# B683X.net
KiCad netlist of a schematic drawn in EAGLE
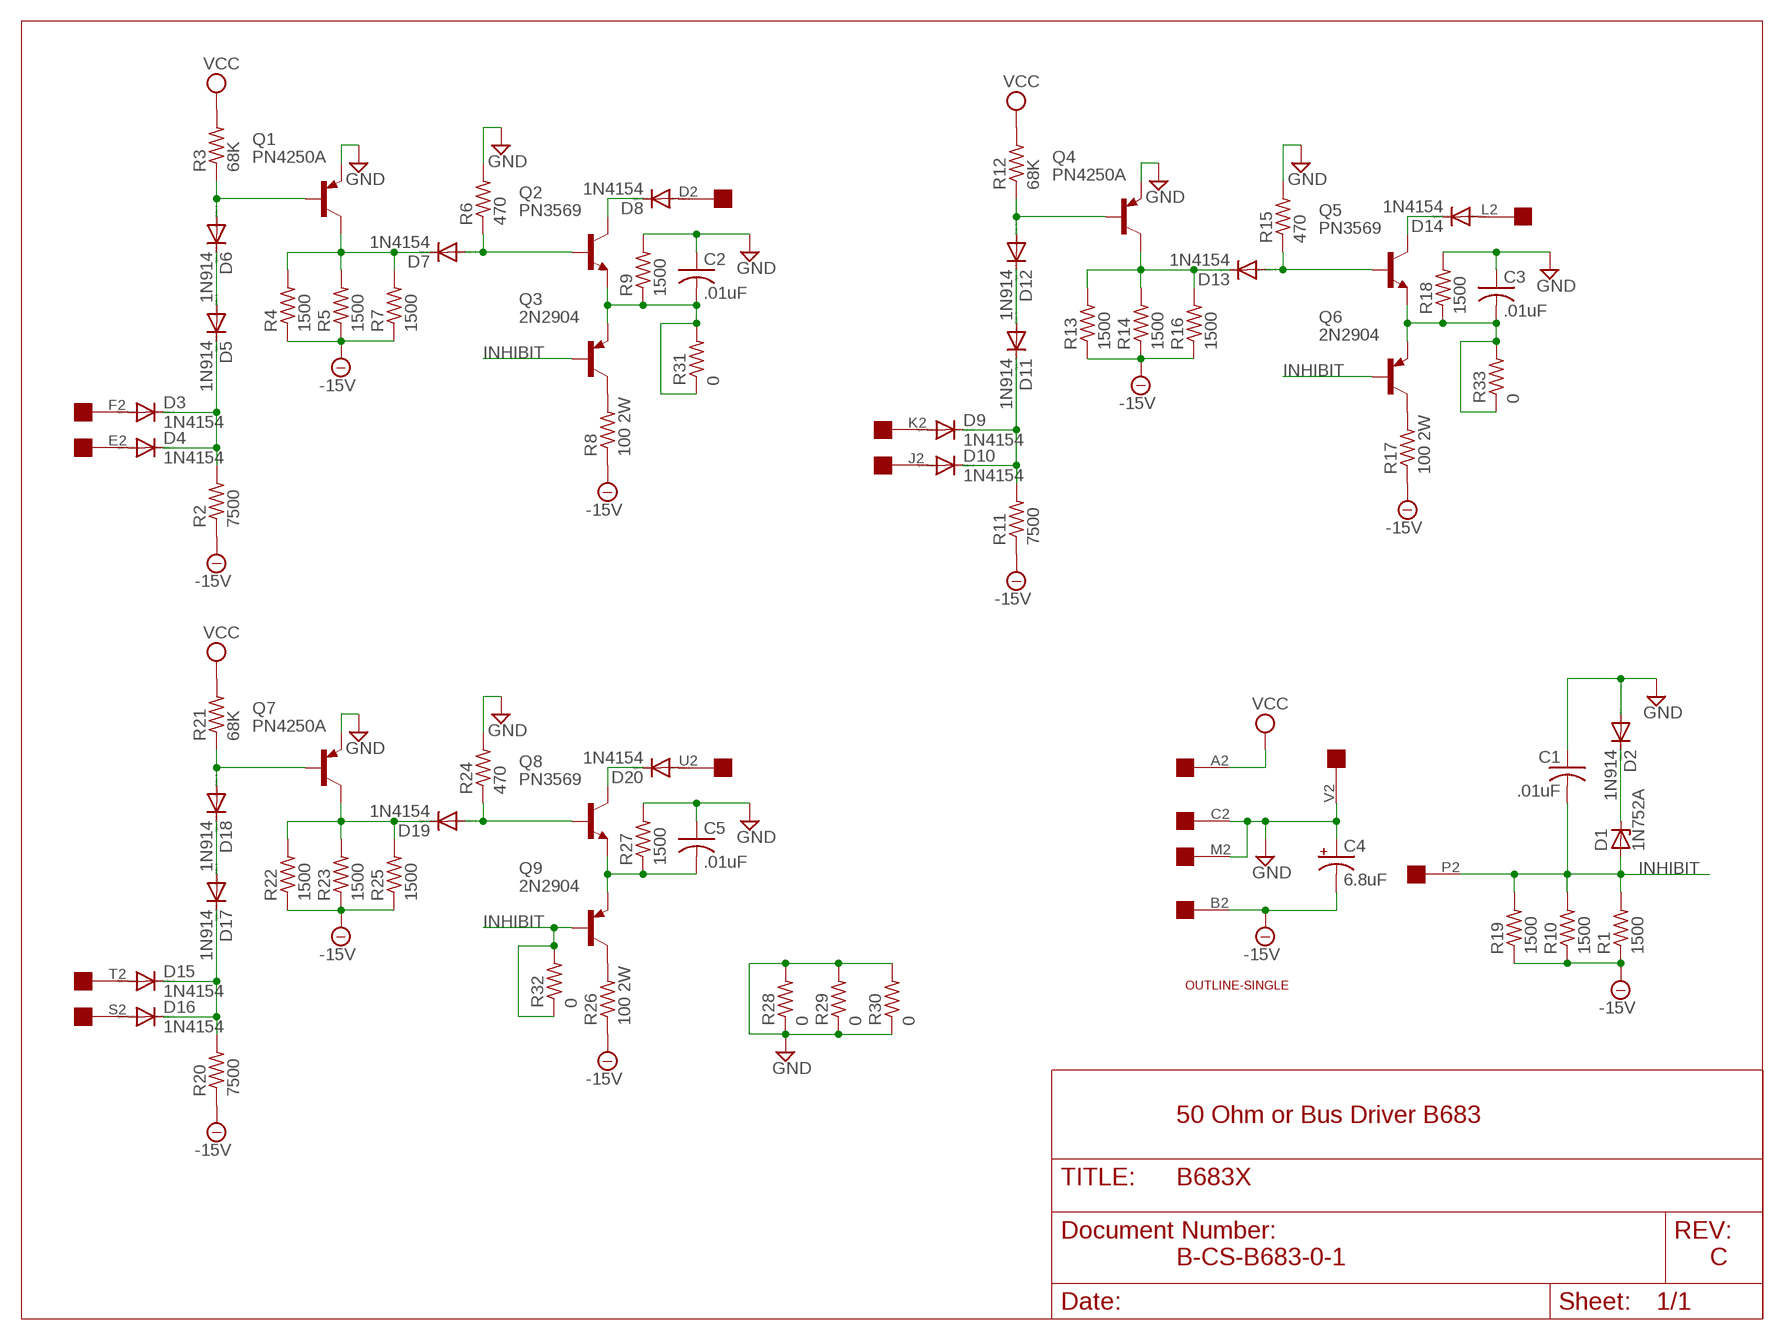
[diagram p0: schematic, sheet 1]

(export (version "E")
  (design (tool "Eeschema 10.0.6"))
  (components
    (comp (ref "C1")
      (value ".01uF")
      (footprint "eagle-import:C063-025X075")
      (libsource (lib "eagle-import") (part "C-US"))
    )
    (comp (ref "C2")
      (value ".01uF")
      (footprint "eagle-import:C063-025X075")
      (libsource (lib "eagle-import") (part "C-US"))
    )
    (comp (ref "C3")
      (value ".01uF")
      (footprint "eagle-import:C063-025X075")
      (libsource (lib "eagle-import") (part "C-US"))
    )
    (comp (ref "C4")
      (value "6.8uF")
      (footprint "eagle-import:E12-8")
      (libsource (lib "eagle-import") (part "CPOL-USE20-8AXIAL"))
    )
    (comp (ref "C5")
      (value ".01uF")
      (footprint "eagle-import:C063-025X075")
      (libsource (lib "eagle-import") (part "C-US"))
    )
    (comp (ref "D1")
      (value "1N752A")
      (footprint "eagle-import:DO35Z10")
      (libsource (lib "eagle-import") (part "ZENER-DIODEDO35Z10"))
    )
    (comp (ref "D2")
      (value "1N914")
      (footprint "eagle-import:DO35-10")
      (libsource (lib "eagle-import") (part "DIODE-DO35-10"))
    )
    (comp (ref "D3")
      (value "1N4154")
      (footprint "eagle-import:DO35-10")
      (libsource (lib "eagle-import") (part "DIODE-DO35-10"))
    )
    (comp (ref "D4")
      (value "1N4154")
      (footprint "eagle-import:DO35-10")
      (libsource (lib "eagle-import") (part "DIODE-DO35-10"))
    )
    (comp (ref "D5")
      (value "1N914")
      (footprint "eagle-import:DO35-10")
      (libsource (lib "eagle-import") (part "DIODE-DO35-10"))
    )
    (comp (ref "D6")
      (value "1N914")
      (footprint "eagle-import:DO35-10")
      (libsource (lib "eagle-import") (part "DIODE-DO35-10"))
    )
    (comp (ref "D7")
      (value "1N4154")
      (footprint "eagle-import:DO35-10")
      (libsource (lib "eagle-import") (part "DIODE-DO35-10"))
    )
    (comp (ref "D8")
      (value "1N4154")
      (footprint "eagle-import:DO35-10")
      (libsource (lib "eagle-import") (part "DIODE-DO35-10"))
    )
    (comp (ref "D9")
      (value "1N4154")
      (footprint "eagle-import:DO35-10")
      (libsource (lib "eagle-import") (part "DIODE-DO35-10"))
    )
    (comp (ref "D10")
      (value "1N4154")
      (footprint "eagle-import:DO35-10")
      (libsource (lib "eagle-import") (part "DIODE-DO35-10"))
    )
    (comp (ref "D11")
      (value "1N914")
      (footprint "eagle-import:DO35-10")
      (libsource (lib "eagle-import") (part "DIODE-DO35-10"))
    )
    (comp (ref "D12")
      (value "1N914")
      (footprint "eagle-import:DO35-10")
      (libsource (lib "eagle-import") (part "DIODE-DO35-10"))
    )
    (comp (ref "D13")
      (value "1N4154")
      (footprint "eagle-import:DO35-10")
      (libsource (lib "eagle-import") (part "DIODE-DO35-10"))
    )
    (comp (ref "D14")
      (value "1N4154")
      (footprint "eagle-import:DO35-10")
      (libsource (lib "eagle-import") (part "DIODE-DO35-10"))
    )
    (comp (ref "D15")
      (value "1N4154")
      (footprint "eagle-import:DO35-10")
      (libsource (lib "eagle-import") (part "DIODE-DO35-10"))
    )
    (comp (ref "D16")
      (value "1N4154")
      (footprint "eagle-import:DO35-10")
      (libsource (lib "eagle-import") (part "DIODE-DO35-10"))
    )
    (comp (ref "D17")
      (value "1N914")
      (footprint "eagle-import:DO35-10")
      (libsource (lib "eagle-import") (part "DIODE-DO35-10"))
    )
    (comp (ref "D18")
      (value "1N914")
      (footprint "eagle-import:DO35-10")
      (libsource (lib "eagle-import") (part "DIODE-DO35-10"))
    )
    (comp (ref "D19")
      (value "1N4154")
      (footprint "eagle-import:DO35-10")
      (libsource (lib "eagle-import") (part "DIODE-DO35-10"))
    )
    (comp (ref "D20")
      (value "1N4154")
      (footprint "eagle-import:DO35-10")
      (libsource (lib "eagle-import") (part "DIODE-DO35-10"))
    )
    (comp (ref "Q1")
      (value "PN4250A")
      (footprint "eagle-import:TO5")
      (libsource (lib "eagle-import") (part "-PNP-TO5"))
    )
    (comp (ref "Q2")
      (value "PN3569")
      (footprint "eagle-import:TO5")
      (libsource (lib "eagle-import") (part "-NPN-TO5"))
    )
    (comp (ref "Q3")
      (value "2N2904")
      (footprint "eagle-import:TO5")
      (libsource (lib "eagle-import") (part "-PNP-TO5"))
    )
    (comp (ref "Q4")
      (value "PN4250A")
      (footprint "eagle-import:TO5")
      (libsource (lib "eagle-import") (part "-PNP-TO5"))
    )
    (comp (ref "Q5")
      (value "PN3569")
      (footprint "eagle-import:TO5")
      (libsource (lib "eagle-import") (part "-NPN-TO5"))
    )
    (comp (ref "Q6")
      (value "2N2904")
      (footprint "eagle-import:TO5")
      (libsource (lib "eagle-import") (part "-PNP-TO5"))
    )
    (comp (ref "Q7")
      (value "PN4250A")
      (footprint "eagle-import:TO5")
      (libsource (lib "eagle-import") (part "-PNP-TO5"))
    )
    (comp (ref "Q8")
      (value "PN3569")
      (footprint "eagle-import:TO5")
      (libsource (lib "eagle-import") (part "-NPN-TO5"))
    )
    (comp (ref "Q9")
      (value "2N2904")
      (footprint "eagle-import:TO5")
      (libsource (lib "eagle-import") (part "-PNP-TO5"))
    )
    (comp (ref "R1")
      (value "1500")
      (footprint "eagle-import:0207_10")
      (libsource (lib "eagle-import") (part "R-US_0207/10"))
    )
    (comp (ref "R2")
      (value "7500")
      (footprint "eagle-import:0207_10")
      (libsource (lib "eagle-import") (part "R-US_0207/10"))
    )
    (comp (ref "R3")
      (value "68K")
      (footprint "eagle-import:0207_10")
      (libsource (lib "eagle-import") (part "R-US_0207/10"))
    )
    (comp (ref "R4")
      (value "1500")
      (footprint "eagle-import:0207_10")
      (libsource (lib "eagle-import") (part "R-US_0207/10"))
    )
    (comp (ref "R5")
      (value "1500")
      (footprint "eagle-import:0207_10")
      (libsource (lib "eagle-import") (part "R-US_0207/10"))
    )
    (comp (ref "R6")
      (value "470")
      (footprint "eagle-import:0207_10")
      (libsource (lib "eagle-import") (part "R-US_0207/10"))
    )
    (comp (ref "R7")
      (value "1500")
      (footprint "eagle-import:0207_10")
      (libsource (lib "eagle-import") (part "R-US_0207/10"))
    )
    (comp (ref "R8")
      (value "100 2W")
      (footprint "eagle-import:0818_25")
      (libsource (lib "eagle-import") (part "R-US_0818/25"))
    )
    (comp (ref "R9")
      (value "1500")
      (footprint "eagle-import:0207_10")
      (libsource (lib "eagle-import") (part "R-US_0207/10"))
    )
    (comp (ref "R10")
      (value "1500")
      (footprint "eagle-import:0207_10")
      (libsource (lib "eagle-import") (part "R-US_0207/10"))
    )
    (comp (ref "R11")
      (value "7500")
      (footprint "eagle-import:0207_10")
      (libsource (lib "eagle-import") (part "R-US_0207/10"))
    )
    (comp (ref "R12")
      (value "68K")
      (footprint "eagle-import:0207_10")
      (libsource (lib "eagle-import") (part "R-US_0207/10"))
    )
    (comp (ref "R13")
      (value "1500")
      (footprint "eagle-import:0207_10")
      (libsource (lib "eagle-import") (part "R-US_0207/10"))
    )
    (comp (ref "R14")
      (value "1500")
      (footprint "eagle-import:0207_10")
      (libsource (lib "eagle-import") (part "R-US_0207/10"))
    )
    (comp (ref "R15")
      (value "470")
      (footprint "eagle-import:0207_10")
      (libsource (lib "eagle-import") (part "R-US_0207/10"))
    )
    (comp (ref "R16")
      (value "1500")
      (footprint "eagle-import:0207_10")
      (libsource (lib "eagle-import") (part "R-US_0207/10"))
    )
    (comp (ref "R17")
      (value "100 2W")
      (footprint "eagle-import:0818_25")
      (libsource (lib "eagle-import") (part "R-US_0818/25"))
    )
    (comp (ref "R18")
      (value "1500")
      (footprint "eagle-import:0207_10")
      (libsource (lib "eagle-import") (part "R-US_0207/10"))
    )
    (comp (ref "R19")
      (value "1500")
      (footprint "eagle-import:0207_10")
      (libsource (lib "eagle-import") (part "R-US_0207/10"))
    )
    (comp (ref "R20")
      (value "7500")
      (footprint "eagle-import:0207_10")
      (libsource (lib "eagle-import") (part "R-US_0207/10"))
    )
    (comp (ref "R21")
      (value "68K")
      (footprint "eagle-import:0207_10")
      (libsource (lib "eagle-import") (part "R-US_0207/10"))
    )
    (comp (ref "R22")
      (value "1500")
      (footprint "eagle-import:0207_10")
      (libsource (lib "eagle-import") (part "R-US_0207/10"))
    )
    (comp (ref "R23")
      (value "1500")
      (footprint "eagle-import:0207_10")
      (libsource (lib "eagle-import") (part "R-US_0207/10"))
    )
    (comp (ref "R24")
      (value "470")
      (footprint "eagle-import:0207_10")
      (libsource (lib "eagle-import") (part "R-US_0207/10"))
    )
    (comp (ref "R25")
      (value "1500")
      (footprint "eagle-import:0207_10")
      (libsource (lib "eagle-import") (part "R-US_0207/10"))
    )
    (comp (ref "R26")
      (value "100 2W")
      (footprint "eagle-import:0818_25")
      (libsource (lib "eagle-import") (part "R-US_0818/25"))
    )
    (comp (ref "R27")
      (value "1500")
      (footprint "eagle-import:0207_10")
      (libsource (lib "eagle-import") (part "R-US_0207/10"))
    )
    (comp (ref "R28")
      (value "0")
      (footprint "eagle-import:0207_10")
      (libsource (lib "eagle-import") (part "R-US_0207/10"))
    )
    (comp (ref "R29")
      (value "0")
      (footprint "eagle-import:0207_10")
      (libsource (lib "eagle-import") (part "R-US_0207/10"))
    )
    (comp (ref "R30")
      (value "0")
      (footprint "eagle-import:0207_10")
      (libsource (lib "eagle-import") (part "R-US_0207/10"))
    )
    (comp (ref "R31")
      (value "0")
      (footprint "eagle-import:0207_10")
      (libsource (lib "eagle-import") (part "R-US_0207/10"))
    )
    (comp (ref "R32")
      (value "0")
      (footprint "eagle-import:0207_10")
      (libsource (lib "eagle-import") (part "R-US_0207/10"))
    )
    (comp (ref "R33")
      (value "0")
      (footprint "eagle-import:0207_10")
      (libsource (lib "eagle-import") (part "R-US_0207/10"))
    )
    (comp (ref "U$1")
      (value "OUTLINE-SINGLE")
      (footprint "eagle-import:SINGLE")
      (libsource (lib "eagle-import") (part "OUTLINE-SINGLE"))
    )
    (comp (ref "U$2")
      (value "EDGE-1")
      (footprint "eagle-import:EDGE-CON1")
      (libsource (lib "eagle-import") (part "EDGE-1"))
    )
  )
  (nets
    (net (code "1") (name "-15V") (class "Default")
      (node (ref "C4") (pin "-") (pinfunction "-_-") (pintype "passive"))
      (node (ref "R1") (pin "1") (pinfunction "1_1") (pintype "passive"))
      (node (ref "R10") (pin "1") (pinfunction "1_1") (pintype "passive"))
      (node (ref "R11") (pin "1") (pinfunction "1_1") (pintype "passive"))
      (node (ref "R13") (pin "1") (pinfunction "1_1") (pintype "passive"))
      (node (ref "R14") (pin "1") (pinfunction "1_1") (pintype "passive"))
      (node (ref "R16") (pin "1") (pinfunction "1_1") (pintype "passive"))
      (node (ref "R17") (pin "1") (pinfunction "1_1") (pintype "passive"))
      (node (ref "R19") (pin "1") (pinfunction "1_1") (pintype "passive"))
      (node (ref "R2") (pin "1") (pinfunction "1_1") (pintype "passive"))
      (node (ref "R20") (pin "1") (pinfunction "1_1") (pintype "passive"))
      (node (ref "R22") (pin "1") (pinfunction "1_1") (pintype "passive"))
      (node (ref "R23") (pin "1") (pinfunction "1_1") (pintype "passive"))
      (node (ref "R25") (pin "1") (pinfunction "1_1") (pintype "passive"))
      (node (ref "R26") (pin "1") (pinfunction "1_1") (pintype "passive"))
      (node (ref "R4") (pin "1") (pinfunction "1_1") (pintype "passive"))
      (node (ref "R5") (pin "1") (pinfunction "1_1") (pintype "passive"))
      (node (ref "R7") (pin "1") (pinfunction "1_1") (pintype "passive"))
      (node (ref "R8") (pin "1") (pinfunction "1_1") (pintype "passive"))
      (node (ref "U$2") (pin "B2") (pinfunction "1_B2") (pintype "bidirectional"))
    )
    (net (code "2") (name "/INHIBIT") (class "Default")
      (node (ref "C1") (pin "2") (pinfunction "2_2") (pintype "passive"))
      (node (ref "D1") (pin "A") (pinfunction "A_A") (pintype "passive"))
      (node (ref "Q3") (pin "2") (pinfunction "B_2") (pintype "passive"))
      (node (ref "Q6") (pin "2") (pinfunction "B_2") (pintype "passive"))
      (node (ref "Q9") (pin "2") (pinfunction "B_2") (pintype "passive"))
      (node (ref "R1") (pin "2") (pinfunction "2_2") (pintype "passive"))
      (node (ref "R10") (pin "2") (pinfunction "2_2") (pintype "passive"))
      (node (ref "R19") (pin "2") (pinfunction "2_2") (pintype "passive"))
      (node (ref "R32") (pin "1") (pinfunction "1_1") (pintype "passive"))
      (node (ref "R32") (pin "2") (pinfunction "2_2") (pintype "passive"))
      (node (ref "U$2") (pin "P2") (pinfunction "1_P2") (pintype "bidirectional"))
    )
    (net (code "3") (name "GND") (class "Default")
      (node (ref "C1") (pin "1") (pinfunction "1_1") (pintype "passive"))
      (node (ref "C2") (pin "1") (pinfunction "1_1") (pintype "passive"))
      (node (ref "C3") (pin "1") (pinfunction "1_1") (pintype "passive"))
      (node (ref "C4") (pin "+") (pinfunction "+_+") (pintype "passive"))
      (node (ref "C5") (pin "1") (pinfunction "1_1") (pintype "passive"))
      (node (ref "D2") (pin "A") (pinfunction "A_A") (pintype "passive"))
      (node (ref "Q1") (pin "1") (pinfunction "E_1") (pintype "passive"))
      (node (ref "Q4") (pin "1") (pinfunction "E_1") (pintype "passive"))
      (node (ref "Q7") (pin "1") (pinfunction "E_1") (pintype "passive"))
      (node (ref "R15") (pin "2") (pinfunction "2_2") (pintype "passive"))
      (node (ref "R18") (pin "2") (pinfunction "2_2") (pintype "passive"))
      (node (ref "R24") (pin "2") (pinfunction "2_2") (pintype "passive"))
      (node (ref "R27") (pin "2") (pinfunction "2_2") (pintype "passive"))
      (node (ref "R28") (pin "1") (pinfunction "1_1") (pintype "passive"))
      (node (ref "R28") (pin "2") (pinfunction "2_2") (pintype "passive"))
      (node (ref "R29") (pin "1") (pinfunction "1_1") (pintype "passive"))
      (node (ref "R29") (pin "2") (pinfunction "2_2") (pintype "passive"))
      (node (ref "R30") (pin "1") (pinfunction "1_1") (pintype "passive"))
      (node (ref "R30") (pin "2") (pinfunction "2_2") (pintype "passive"))
      (node (ref "R6") (pin "2") (pinfunction "2_2") (pintype "passive"))
      (node (ref "R9") (pin "2") (pinfunction "2_2") (pintype "passive"))
      (node (ref "U$2") (pin "C2") (pinfunction "1_C2") (pintype "bidirectional"))
      (node (ref "U$2") (pin "M2") (pinfunction "1_M2") (pintype "bidirectional"))
      (node (ref "U$2") (pin "V2") (pinfunction "1_V2") (pintype "bidirectional"))
    )
    (net (code "4") (name "Net-(D1-PadC)") (class "Default")
      (node (ref "D1") (pin "C") (pinfunction "C_C") (pintype "passive"))
      (node (ref "D2") (pin "C") (pinfunction "C_C") (pintype "passive"))
    )
    (net (code "5") (name "Net-(D3-PadC)") (class "Default")
      (node (ref "D3") (pin "C") (pinfunction "C_C") (pintype "passive"))
      (node (ref "D4") (pin "C") (pinfunction "C_C") (pintype "passive"))
      (node (ref "D5") (pin "C") (pinfunction "C_C") (pintype "passive"))
      (node (ref "R2") (pin "2") (pinfunction "2_2") (pintype "passive"))
    )
    (net (code "6") (name "Net-(D5-PadA)") (class "Default")
      (node (ref "D5") (pin "A") (pinfunction "A_A") (pintype "passive"))
      (node (ref "D6") (pin "C") (pinfunction "C_C") (pintype "passive"))
    )
    (net (code "7") (name "Net-(D10-PadC)") (class "Default")
      (node (ref "D10") (pin "C") (pinfunction "C_C") (pintype "passive"))
      (node (ref "D11") (pin "C") (pinfunction "C_C") (pintype "passive"))
      (node (ref "D9") (pin "C") (pinfunction "C_C") (pintype "passive"))
      (node (ref "R11") (pin "2") (pinfunction "2_2") (pintype "passive"))
    )
    (net (code "8") (name "Net-(D11-PadA)") (class "Default")
      (node (ref "D11") (pin "A") (pinfunction "A_A") (pintype "passive"))
      (node (ref "D12") (pin "C") (pinfunction "C_C") (pintype "passive"))
    )
    (net (code "9") (name "Net-(D15-PadC)") (class "Default")
      (node (ref "D15") (pin "C") (pinfunction "C_C") (pintype "passive"))
      (node (ref "D16") (pin "C") (pinfunction "C_C") (pintype "passive"))
      (node (ref "D17") (pin "C") (pinfunction "C_C") (pintype "passive"))
      (node (ref "R20") (pin "2") (pinfunction "2_2") (pintype "passive"))
    )
    (net (code "10") (name "Net-(D17-PadA)") (class "Default")
      (node (ref "D17") (pin "A") (pinfunction "A_A") (pintype "passive"))
      (node (ref "D18") (pin "C") (pinfunction "C_C") (pintype "passive"))
    )
    (net (code "11") (name "Net-(Q1-B)") (class "Default")
      (node (ref "D6") (pin "A") (pinfunction "A_A") (pintype "passive"))
      (node (ref "Q1") (pin "2") (pinfunction "B_2") (pintype "passive"))
      (node (ref "R3") (pin "1") (pinfunction "1_1") (pintype "passive"))
    )
    (net (code "12") (name "Net-(Q1-C)") (class "Default")
      (node (ref "D7") (pin "C") (pinfunction "C_C") (pintype "passive"))
      (node (ref "Q1") (pin "3") (pinfunction "C_3") (pintype "passive"))
      (node (ref "R4") (pin "2") (pinfunction "2_2") (pintype "passive"))
      (node (ref "R5") (pin "2") (pinfunction "2_2") (pintype "passive"))
      (node (ref "R7") (pin "2") (pinfunction "2_2") (pintype "passive"))
    )
    (net (code "13") (name "Net-(Q2-B)") (class "Default")
      (node (ref "D7") (pin "A") (pinfunction "A_A") (pintype "passive"))
      (node (ref "Q2") (pin "2") (pinfunction "B_2") (pintype "passive"))
      (node (ref "R6") (pin "1") (pinfunction "1_1") (pintype "passive"))
    )
    (net (code "14") (name "Net-(Q2-C)") (class "Default")
      (node (ref "D8") (pin "C") (pinfunction "C_C") (pintype "passive"))
      (node (ref "Q2") (pin "3") (pinfunction "C_3") (pintype "passive"))
    )
    (net (code "15") (name "Net-(Q2-E)") (class "Default")
      (node (ref "C2") (pin "2") (pinfunction "2_2") (pintype "passive"))
      (node (ref "Q2") (pin "1") (pinfunction "E_1") (pintype "passive"))
      (node (ref "Q3") (pin "1") (pinfunction "E_1") (pintype "passive"))
      (node (ref "R31") (pin "1") (pinfunction "1_1") (pintype "passive"))
      (node (ref "R31") (pin "2") (pinfunction "2_2") (pintype "passive"))
      (node (ref "R9") (pin "1") (pinfunction "1_1") (pintype "passive"))
    )
    (net (code "16") (name "Net-(Q3-C)") (class "Default")
      (node (ref "Q3") (pin "3") (pinfunction "C_3") (pintype "passive"))
      (node (ref "R8") (pin "2") (pinfunction "2_2") (pintype "passive"))
    )
    (net (code "17") (name "Net-(Q4-B)") (class "Default")
      (node (ref "D12") (pin "A") (pinfunction "A_A") (pintype "passive"))
      (node (ref "Q4") (pin "2") (pinfunction "B_2") (pintype "passive"))
      (node (ref "R12") (pin "1") (pinfunction "1_1") (pintype "passive"))
    )
    (net (code "18") (name "Net-(Q4-C)") (class "Default")
      (node (ref "D13") (pin "C") (pinfunction "C_C") (pintype "passive"))
      (node (ref "Q4") (pin "3") (pinfunction "C_3") (pintype "passive"))
      (node (ref "R13") (pin "2") (pinfunction "2_2") (pintype "passive"))
      (node (ref "R14") (pin "2") (pinfunction "2_2") (pintype "passive"))
      (node (ref "R16") (pin "2") (pinfunction "2_2") (pintype "passive"))
    )
    (net (code "19") (name "Net-(Q5-B)") (class "Default")
      (node (ref "D13") (pin "A") (pinfunction "A_A") (pintype "passive"))
      (node (ref "Q5") (pin "2") (pinfunction "B_2") (pintype "passive"))
      (node (ref "R15") (pin "1") (pinfunction "1_1") (pintype "passive"))
    )
    (net (code "20") (name "Net-(Q5-C)") (class "Default")
      (node (ref "D14") (pin "C") (pinfunction "C_C") (pintype "passive"))
      (node (ref "Q5") (pin "3") (pinfunction "C_3") (pintype "passive"))
    )
    (net (code "21") (name "Net-(Q5-E)") (class "Default")
      (node (ref "C3") (pin "2") (pinfunction "2_2") (pintype "passive"))
      (node (ref "Q5") (pin "1") (pinfunction "E_1") (pintype "passive"))
      (node (ref "Q6") (pin "1") (pinfunction "E_1") (pintype "passive"))
      (node (ref "R18") (pin "1") (pinfunction "1_1") (pintype "passive"))
      (node (ref "R33") (pin "1") (pinfunction "1_1") (pintype "passive"))
      (node (ref "R33") (pin "2") (pinfunction "2_2") (pintype "passive"))
    )
    (net (code "22") (name "Net-(Q6-C)") (class "Default")
      (node (ref "Q6") (pin "3") (pinfunction "C_3") (pintype "passive"))
      (node (ref "R17") (pin "2") (pinfunction "2_2") (pintype "passive"))
    )
    (net (code "23") (name "Net-(Q7-B)") (class "Default")
      (node (ref "D18") (pin "A") (pinfunction "A_A") (pintype "passive"))
      (node (ref "Q7") (pin "2") (pinfunction "B_2") (pintype "passive"))
      (node (ref "R21") (pin "1") (pinfunction "1_1") (pintype "passive"))
    )
    (net (code "24") (name "Net-(Q7-C)") (class "Default")
      (node (ref "D19") (pin "C") (pinfunction "C_C") (pintype "passive"))
      (node (ref "Q7") (pin "3") (pinfunction "C_3") (pintype "passive"))
      (node (ref "R22") (pin "2") (pinfunction "2_2") (pintype "passive"))
      (node (ref "R23") (pin "2") (pinfunction "2_2") (pintype "passive"))
      (node (ref "R25") (pin "2") (pinfunction "2_2") (pintype "passive"))
    )
    (net (code "25") (name "Net-(Q8-B)") (class "Default")
      (node (ref "D19") (pin "A") (pinfunction "A_A") (pintype "passive"))
      (node (ref "Q8") (pin "2") (pinfunction "B_2") (pintype "passive"))
      (node (ref "R24") (pin "1") (pinfunction "1_1") (pintype "passive"))
    )
    (net (code "26") (name "Net-(Q8-C)") (class "Default")
      (node (ref "D20") (pin "C") (pinfunction "C_C") (pintype "passive"))
      (node (ref "Q8") (pin "3") (pinfunction "C_3") (pintype "passive"))
    )
    (net (code "27") (name "Net-(Q8-E)") (class "Default")
      (node (ref "C5") (pin "2") (pinfunction "2_2") (pintype "passive"))
      (node (ref "Q8") (pin "1") (pinfunction "E_1") (pintype "passive"))
      (node (ref "Q9") (pin "1") (pinfunction "E_1") (pintype "passive"))
      (node (ref "R27") (pin "1") (pinfunction "1_1") (pintype "passive"))
    )
    (net (code "28") (name "Net-(Q9-C)") (class "Default")
      (node (ref "Q9") (pin "3") (pinfunction "C_3") (pintype "passive"))
      (node (ref "R26") (pin "2") (pinfunction "2_2") (pintype "passive"))
    )
    (net (code "29") (name "Net-(U$2D-1)") (class "Default")
      (node (ref "D8") (pin "A") (pinfunction "A_A") (pintype "passive"))
      (node (ref "U$2") (pin "D2") (pinfunction "1_D2") (pintype "bidirectional"))
    )
    (net (code "30") (name "Net-(U$2E-1)") (class "Default")
      (node (ref "D4") (pin "A") (pinfunction "A_A") (pintype "passive"))
      (node (ref "U$2") (pin "E2") (pinfunction "1_E2") (pintype "bidirectional"))
    )
    (net (code "31") (name "Net-(U$2F-1)") (class "Default")
      (node (ref "D3") (pin "A") (pinfunction "A_A") (pintype "passive"))
      (node (ref "U$2") (pin "F2") (pinfunction "1_F2") (pintype "bidirectional"))
    )
    (net (code "32") (name "Net-(U$2H-1)") (class "Default")
      (node (ref "D10") (pin "A") (pinfunction "A_A") (pintype "passive"))
      (node (ref "U$2") (pin "J2") (pinfunction "1_J2") (pintype "bidirectional"))
    )
    (net (code "33") (name "Net-(U$2I-1)") (class "Default")
      (node (ref "D9") (pin "A") (pinfunction "A_A") (pintype "passive"))
      (node (ref "U$2") (pin "K2") (pinfunction "1_K2") (pintype "bidirectional"))
    )
    (net (code "34") (name "Net-(U$2J-1)") (class "Default")
      (node (ref "D14") (pin "A") (pinfunction "A_A") (pintype "passive"))
      (node (ref "U$2") (pin "L2") (pinfunction "1_L2") (pintype "bidirectional"))
    )
    (net (code "35") (name "Net-(U$2O-1)") (class "Default")
      (node (ref "D16") (pin "A") (pinfunction "A_A") (pintype "passive"))
      (node (ref "U$2") (pin "S2") (pinfunction "1_S2") (pintype "bidirectional"))
    )
    (net (code "36") (name "Net-(U$2P-1)") (class "Default")
      (node (ref "D15") (pin "A") (pinfunction "A_A") (pintype "passive"))
      (node (ref "U$2") (pin "T2") (pinfunction "1_T2") (pintype "bidirectional"))
    )
    (net (code "37") (name "Net-(U$2Q-1)") (class "Default")
      (node (ref "D20") (pin "A") (pinfunction "A_A") (pintype "passive"))
      (node (ref "U$2") (pin "U2") (pinfunction "1_U2") (pintype "bidirectional"))
    )
    (net (code "38") (name "VCC") (class "Default")
      (node (ref "R12") (pin "2") (pinfunction "2_2") (pintype "passive"))
      (node (ref "R21") (pin "2") (pinfunction "2_2") (pintype "passive"))
      (node (ref "R3") (pin "2") (pinfunction "2_2") (pintype "passive"))
      (node (ref "U$2") (pin "A2") (pinfunction "1_A2") (pintype "bidirectional"))
    )
  )
)
